# Sheet_f446.net
KiCad netlist of a schematic drawn in Altium Designer
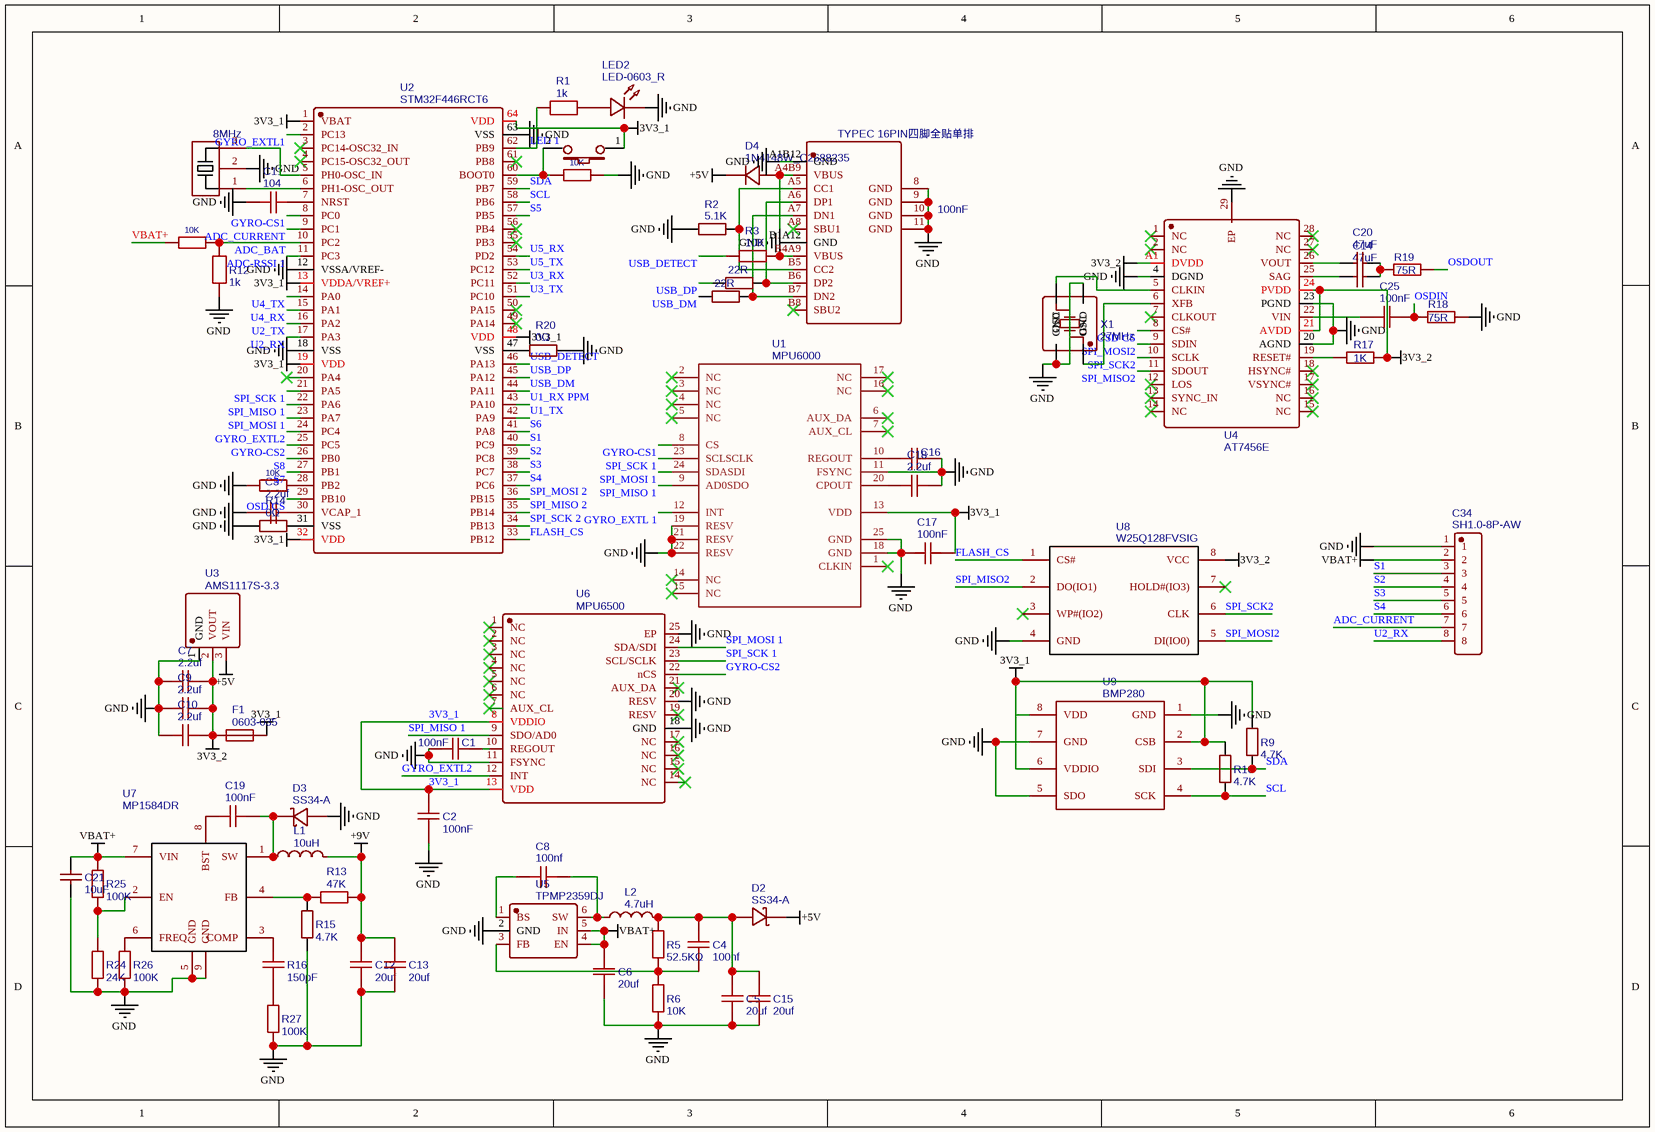
[diagram p0: Sheet_f446.schdoc]

(export (version "E")
  (design (tool "Eeschema 10.0.6"))
  (components
    (comp (ref "BOOT1")
      (value "两脚小龟 3*4*2")
      (fields (field (name "BOM_SUPPLIER PART") "C2837315") (field (name "CONTRIBUTOR") "LCSC"))
      (libsource (lib "altium-import") (part "root_2_两脚小龟 3*4*2_"))
    )
    (comp (ref "C1")
      (value "100nF")
      (fields
        (field (name "BOM_MANUFACTURER PART") "GRM155F50J104ZA01D")
        (field (name "BOM_SUPPLIER PART") "C85956")
      )
      (libsource (lib "altium-import") (part "root_0_100nF_"))
    )
    (comp (ref "C2")
      (value "100nF")
      (fields
        (field (name "BOM_MANUFACTURER PART") "GRM155F50J104ZA01D")
        (field (name "BOM_SUPPLIER PART") "C85956")
      )
      (libsource (lib "altium-import") (part "root_1_100nF_"))
    )
    (comp (ref "C3")
      (value "2.2uf")
      (fields (field (name "CONTRIBUTOR") "LCEDA_Lib"))
      (libsource (lib "altium-import") (part "root_2_2.2uf_"))
    )
    (comp (ref "C4")
      (value "100nf")
      (fields (field (name "BOM_MANUFACTURER PART") "CC0603FRNPO9BN201") (field (name "CONTRIBUTOR") "LCSC"))
      (libsource (lib "altium-import") (part "root_3_100nf_"))
    )
    (comp (ref "C5")
      (value "20uf")
      (fields (field (name "BOM_MANUFACTURER PART") "CC0603FRNPO9BN201") (field (name "CONTRIBUTOR") "LCSC"))
      (libsource (lib "altium-import") (part "root_3_20uf_"))
    )
    (comp (ref "C6")
      (value "20uf")
      (fields (field (name "BOM_MANUFACTURER PART") "CC0603FRNPO9BN201") (field (name "CONTRIBUTOR") "LCSC"))
      (libsource (lib "altium-import") (part "root_1_20uf_"))
    )
    (comp (ref "C7")
      (value "2.2uf")
      (fields (field (name "CONTRIBUTOR") "LCEDA_Lib"))
      (libsource (lib "altium-import") (part "root_0_2.2uf_"))
    )
    (comp (ref "C8")
      (value "100nf")
      (fields (field (name "BOM_MANUFACTURER PART") "CC0603FRNPO9BN201") (field (name "CONTRIBUTOR") "LCSC"))
      (libsource (lib "altium-import") (part "root_2_100nf_"))
    )
    (comp (ref "C9")
      (value "2.2uf")
      (fields (field (name "CONTRIBUTOR") "LCEDA_Lib"))
      (libsource (lib "altium-import") (part "root_2_2.2uf_"))
    )
    (comp (ref "C10")
      (value "2.2uf")
      (fields (field (name "CONTRIBUTOR") "LCEDA_Lib"))
      (libsource (lib "altium-import") (part "root_2_2.2uf_"))
    )
    (comp (ref "C11")
      (value "104")
      (fields (field (name "CONTRIBUTOR") "LCEDA_Lib"))
      (libsource (lib "altium-import") (part "root_2_104_"))
    )
    (comp (ref "C12")
      (value "20uf")
      (fields (field (name "BOM_MANUFACTURER PART") "CC0603FRNPO9BN201") (field (name "CONTRIBUTOR") "LCSC"))
      (libsource (lib "altium-import") (part "root_1_20uf_"))
    )
    (comp (ref "C13")
      (value "20uf")
      (fields (field (name "BOM_MANUFACTURER PART") "CC0603FRNPO9BN201") (field (name "CONTRIBUTOR") "LCSC"))
      (libsource (lib "altium-import") (part "root_1_20uf_"))
    )
    (comp (ref "C14")
      (value "47uF")
      (fields
        (field (name "BOM_MANUFACTURER PART") "CL21A476MQYNNNE")
        (field (name "BOM_SUPPLIER PART") "C16780")
      )
      (libsource (lib "altium-import") (part "root_0_47uF_"))
    )
    (comp (ref "C15")
      (value "20uf")
      (fields (field (name "BOM_MANUFACTURER PART") "CC0603FRNPO9BN201") (field (name "CONTRIBUTOR") "LCSC"))
      (libsource (lib "altium-import") (part "root_1_20uf_"))
    )
    (comp (ref "C16")
      (value "100nF")
      (fields
        (field (name "BOM_MANUFACTURER PART") "GRM155F50J104ZA01D")
        (field (name "BOM_SUPPLIER PART") "C85956")
      )
      (libsource (lib "altium-import") (part "root_0_100nF_"))
    )
    (comp (ref "C17")
      (value "100nF")
      (fields
        (field (name "BOM_MANUFACTURER PART") "GRM155F50J104ZA01D")
        (field (name "BOM_SUPPLIER PART") "C85956")
      )
      (libsource (lib "altium-import") (part "root_0_100nF_"))
    )
    (comp (ref "C18")
      (value "2.2uf")
      (fields (field (name "CONTRIBUTOR") "LCEDA_Lib"))
      (libsource (lib "altium-import") (part "root_0_2.2uf_"))
    )
    (comp (ref "C19")
      (value "100nF")
      (fields
        (field (name "BOM_MANUFACTURER PART") "CC0603KRX7R9BB104")
        (field (name "BOM_SUPPLIER PART") "C14663")
      )
      (libsource (lib "altium-import") (part "root_0_100nF_"))
    )
    (comp (ref "C20")
      (value "47uF")
      (fields
        (field (name "BOM_MANUFACTURER PART") "CL21A476MQYNNNE")
        (field (name "BOM_SUPPLIER PART") "C16780")
      )
      (libsource (lib "altium-import") (part "root_0_47uF_"))
    )
    (comp (ref "C21")
      (value "10uF")
      (fields
        (field (name "BOM_MANUFACTURER PART") "1206F106M500NT")
        (field (name "BOM_SUPPLIER PART") "C110256")
      )
      (libsource (lib "altium-import") (part "root_1_10uF_"))
    )
    (comp (ref "C25")
      (value "100nF")
      (fields
        (field (name "BOM_MANUFACTURER PART") "0402B104K500")
        (field (name "BOM_SUPPLIER PART") "C152814")
        (field (name "CONTRIBUTOR") "LCSC")
      )
      (libsource (lib "") (part "root_0_100nF__1"))
    )
    (comp (ref "C34")
      (value "SH1.0-8P-AW")
      (fields (field (name "CONTRIBUTOR") "xiogua"))
      (libsource (lib "altium-import") (part "root_0_SH1.0-8P-AW_"))
    )
    (comp (ref "D2")
      (value "SS34-A")
      (fields (field (name "BOM_SUPPLIER PART") "C143201") (field (name "CONTRIBUTOR") "LCSC"))
      (libsource (lib "altium-import") (part "root_2_SS34-A_"))
    )
    (comp (ref "D3")
      (value "SS34-A")
      (fields (field (name "BOM_SUPPLIER PART") "C143201") (field (name "CONTRIBUTOR") "LCSC"))
      (libsource (lib "altium-import") (part "root_0_SS34-A_"))
    )
    (comp (ref "D4")
      (value "1N4148W_C2688235")
      (fields
        (field (name "BOM_SUPPLIER PART") "C2688235")
        (field (name "BOM_MANUFACTURER PART") "1N4148W")
        (field (name "CONTRIBUTOR") "LCSC")
      )
      (libsource (lib "altium-import") (part "root_0_1N4148W_C2688235_"))
    )
    (comp (ref "F1")
      (value "0603-035")
      (fields (field (name "BOM_SUPPLIER PART") "C70051"))
      (libsource (lib "altium-import") (part "root_0_0603-035_"))
    )
    (comp (ref "L1")
      (value "10uH")
      (fields
        (field (name "BOM_MANUFACTURER PART") "MCW-0530-100-N1")
        (field (name "BOM_SUPPLIER PART") "C169352")
        (field (name "CONTRIBUTOR") "LCSC")
      )
      (libsource (lib "altium-import") (part "root_0_10uH_"))
    )
    (comp (ref "L2")
      (value "4.7uH")
      (fields
        (field (name "BOM_SUPPLIER PART") "C477143")
        (field (name "BOM_MANUFACTURER PART") "GPSR0420-4R7MS01")
        (field (name "CONTRIBUTOR") "LCSC")
      )
      (libsource (lib "altium-import") (part "root_0_4.7uH_"))
    )
    (comp (ref "LED2")
      (value "LED-0603_R")
      (fields
        (field (name "BOM_MANUFACTURER PART") "19-217/R6C-AL1M2VY/3T")
        (field (name "BOM_SUPPLIER PART") "C72044")
        (field (name "CONTRIBUTOR") "LCEDA_01")
      )
      (libsource (lib "altium-import") (part "root_0_LED-0603_R_"))
    )
    (comp (ref "NO")
      (value "TYPEC 16PIN四脚全贴单排")
      (fields (field (name "BOM_SUPPLIER PART") "C9900003589") (field (name "CONTRIBUTOR") "LCSC"))
      (libsource (lib "altium-import") (part "root_0_TYPEC 16PIN四脚全贴单排_"))
    )
    (comp (ref "R1")
      (value "1k")
      (fields (field (name "CONTRIBUTOR") "LCEDA_Lib"))
      (libsource (lib "altium-import") (part "root_0_1k_"))
    )
    (comp (ref "R2")
      (value "5.1K")
      (fields
        (field (name "BOM_MANUFACTURER PART") "RC0402DR-075K1L")
        (field (name "BOM_SUPPLIER PART") "C138073")
      )
      (libsource (lib "altium-import") (part "root_0_5.1K_"))
    )
    (comp (ref "R3")
      (value "10K")
      (fields
        (field (name "BOM_SUPPLIER PART") "C144807")
        (field (name "BOM_MANUFACTURER PART") "AC0402FR-0710KL")
        (field (name "CONTRIBUTOR") "LCSC")
      )
      (libsource (lib "altium-import") (part "root_0_10K_"))
    )
    (comp (ref "R4")
      (value "10K")
      (fields
        (field (name "BOM_SUPPLIER PART") "C84351")
        (field (name "BOM_MANUFACTURER PART") "TC0225B1002TCE")
        (field (name "CONTRIBUTOR") "LCSC")
      )
      (libsource (lib "altium-import") (part "root_2_10K_"))
    )
    (comp (ref "R5")
      (value "52.5KΩ")
      (fields
        (field (name "BOM_SUPPLIER PART") "C114978")
        (field (name "BOM_MANUFACTURER PART") "0402WGF523JTCE")
        (field (name "CONTRIBUTOR") "LCSC")
      )
      (libsource (lib "altium-import") (part "root_1_52.5KΩ_"))
    )
    (comp (ref "R6")
      (value "10K")
      (fields
        (field (name "BOM_MANUFACTURER PART") "AC0402JR-0710KL")
        (field (name "BOM_SUPPLIER PART") "C144731")
        (field (name "CONTRIBUTOR") "LCSC")
      )
      (libsource (lib "altium-import") (part "root_1_10K_"))
    )
    (comp (ref "R8")
      (value "10K")
      (fields
        (field (name "BOM_SUPPLIER PART") "C84351")
        (field (name "BOM_MANUFACTURER PART") "TC0225B1002TCE")
        (field (name "CONTRIBUTOR") "LCSC")
      )
      (libsource (lib "altium-import") (part "root_0_10K_"))
    )
    (comp (ref "R9")
      (value "4.7K")
      (fields
        (field (name "BOM_MANUFACTURER PART") "RC0402FR-074K7L")
        (field (name "BOM_SUPPLIER PART") "C105871")
      )
      (libsource (lib "altium-import") (part "root_1_4.7K_"))
    )
    (comp (ref "R10")
      (value "4.7K")
      (fields
        (field (name "BOM_MANUFACTURER PART") "RC0402FR-074K7L")
        (field (name "BOM_SUPPLIER PART") "C105871")
      )
      (libsource (lib "altium-import") (part "root_1_4.7K_"))
    )
    (comp (ref "R11")
      (value "10K")
      (fields
        (field (name "BOM_SUPPLIER PART") "C84351")
        (field (name "BOM_MANUFACTURER PART") "TC0225B1002TCE")
        (field (name "CONTRIBUTOR") "LCSC")
      )
      (libsource (lib "altium-import") (part "root_2_10K_"))
    )
    (comp (ref "R12")
      (value "1k")
      (fields (field (name "CONTRIBUTOR") "LCEDA_Lib"))
      (libsource (lib "altium-import") (part "root_1_1k_"))
    )
    (comp (ref "R13")
      (value "47K")
      (fields
        (field (name "BOM_MANUFACTURER PART") "AC0402JR-0747KL")
        (field (name "BOM_SUPPLIER PART") "C144710")
        (field (name "CONTRIBUTOR") "LCSC")
      )
      (libsource (lib "altium-import") (part "root_0_47K_"))
    )
    (comp (ref "R14")
      (value "0Ω")
      (fields (field (name "CONTRIBUTOR") "微客"))
      (libsource (lib "altium-import") (part "root_0_0Ω_"))
    )
    (comp (ref "R15")
      (value "4.7K")
      (fields
        (field (name "BOM_MANUFACTURER PART") "RC0402FR-074K7L")
        (field (name "BOM_SUPPLIER PART") "C105871")
      )
      (libsource (lib "altium-import") (part "root_1_4.7K_"))
    )
    (comp (ref "R16")
      (value "150pF")
      (fields
        (field (name "BOM_SUPPLIER PART") "C1623917")
        (field (name "BOM_MANUFACTURER PART") "C0402C151J8JAC7867")
        (field (name "CONTRIBUTOR") "LCSC")
      )
      (libsource (lib "altium-import") (part "root_1_150pF_"))
    )
    (comp (ref "R17")
      (value "1K")
      (fields
        (field (name "BOM_SUPPLIER PART") "C279987")
        (field (name "BOM_MANUFACTURER PART") "CR-02JL6----1K")
        (field (name "CONTRIBUTOR") "LCSC")
      )
      (libsource (lib "altium-import") (part "root_0_1K_"))
    )
    (comp (ref "R18")
      (value "75R")
      (fields
        (field (name "BOM_SUPPLIER PART") "C174263")
        (field (name "BOM_MANUFACTURER PART") "RCT0275RJLF")
        (field (name "CONTRIBUTOR") "LCSC")
      )
      (libsource (lib "altium-import") (part "root_0_75R_"))
    )
    (comp (ref "R19")
      (value "75R")
      (fields
        (field (name "BOM_SUPPLIER PART") "C174263")
        (field (name "BOM_MANUFACTURER PART") "RCT0275RJLF")
        (field (name "CONTRIBUTOR") "LCSC")
      )
      (libsource (lib "altium-import") (part "root_0_75R_"))
    )
    (comp (ref "R20")
      (value "0Ω")
      (fields (field (name "CONTRIBUTOR") "微客"))
      (libsource (lib "altium-import") (part "root_0_0Ω_"))
    )
    (comp (ref "R21")
      (value "22R")
      (fields
        (field (name "BOM_MANUFACTURER PART") "RM04FTN22R0")
        (field (name "BOM_SUPPLIER PART") "C153098")
      )
      (libsource (lib "altium-import") (part "root_2_22R_"))
    )
    (comp (ref "R22")
      (value "22R")
      (fields
        (field (name "BOM_MANUFACTURER PART") "RM04FTN22R0")
        (field (name "BOM_SUPPLIER PART") "C153098")
      )
      (libsource (lib "altium-import") (part "root_2_22R_"))
    )
    (comp (ref "R24")
      (value "24K")
      (fields
        (field (name "BOM_SUPPLIER PART") "C227339")
        (field (name "BOM_MANUFACTURER PART") "AC0402JR-0724KL")
        (field (name "CONTRIBUTOR") "LCSC")
      )
      (libsource (lib "altium-import") (part "root_1_24K_"))
    )
    (comp (ref "R25")
      (value "100K")
      (fields
        (field (name "BOM_MANUFACTURER PART") "AC0402JR-07100KL")
        (field (name "BOM_SUPPLIER PART") "C144732")
        (field (name "CONTRIBUTOR") "LCSC")
      )
      (libsource (lib "altium-import") (part "root_1_100K_"))
    )
    (comp (ref "R26")
      (value "100K")
      (fields
        (field (name "BOM_MANUFACTURER PART") "AC0402JR-07100KL")
        (field (name "BOM_SUPPLIER PART") "C144732")
        (field (name "CONTRIBUTOR") "LCSC")
      )
      (libsource (lib "altium-import") (part "root_1_100K_"))
    )
    (comp (ref "R27")
      (value "100K")
      (fields
        (field (name "BOM_MANUFACTURER PART") "AC0402JR-07100KL")
        (field (name "BOM_SUPPLIER PART") "C144732")
        (field (name "CONTRIBUTOR") "LCSC")
      )
      (libsource (lib "altium-import") (part "root_1_100K_"))
    )
    (comp (ref "U1")
      (value "MPU6000")
      (fields (field (name "CONTRIBUTOR") "msnrooon"))
      (libsource (lib "altium-import") (part "root_0_MPU6000_"))
    )
    (comp (ref "U2")
      (value "STM32F446RCT6")
      (fields (field (name "BOM_SUPPLIER PART") "C915971") (field (name "CONTRIBUTOR") "LCSC"))
      (libsource (lib "altium-import") (part "root_0_STM32F446RCT6_"))
    )
    (comp (ref "U3")
      (value "AMS1117S-3.3")
      (fields (field (name "BOM_SUPPLIER PART") "C917152") (field (name "CONTRIBUTOR") "LCSC"))
      (libsource (lib "altium-import") (part "root_1_AMS1117S-3.3_"))
    )
    (comp (ref "U4")
      (value "AT7456E")
      (fields (field (name "BOM_SUPPLIER PART") "C82351"))
      (libsource (lib "altium-import") (part "root_0_AT7456E_"))
    )
    (comp (ref "U5")
      (value "TPMP2359DJ")
      (fields (field (name "BOM_SUPPLIER PART") "C2959845") (field (name "CONTRIBUTOR") "LCSC"))
      (libsource (lib "altium-import") (part "root_0_TPMP2359DJ_"))
    )
    (comp (ref "U6")
      (value "MPU6500")
      (fields (field (name "BOM_SUPPLIER PART") "C50278"))
      (libsource (lib "altium-import") (part "root_0_MPU6500_"))
    )
    (comp (ref "U7")
      (value "MP1584DR")
      (fields (field (name "CONTRIBUTOR") "chejia12"))
      (libsource (lib "altium-import") (part "root_0_MP1584DR_"))
    )
    (comp (ref "U8")
      (value "W25Q128FVSIG")
      (fields (field (name "BOM_SUPPLIER PART") "C35101"))
      (libsource (lib "altium-import") (part "root_0_W25Q128FVSIG_"))
    )
    (comp (ref "U9")
      (value "BMP280")
      (fields (field (name "BOM_SUPPLIER PART") "C83291"))
      (libsource (lib "altium-import") (part "root_0_BMP280_"))
    )
    (comp (ref "X1")
      (value "27MHz")
      (fields
        (field (name "BOM_SUPPLIER PART") "C438902")
        (field (name "BOM_MANUFACTURER PART") "NX2016SA-STD-CZS-5-27MHZ")
        (field (name "CONTRIBUTOR") "LCSC")
      )
      (libsource (lib "altium-import") (part "root_1_27MHz_"))
    )
    (comp (ref "X3")
      (value "8MHz")
      (fields
        (field (name "BOM_MANUFACTURER PART") "CSTCE8M00G55A-R0")
        (field (name "BOM_SUPPLIER PART") "C91587")
      )
      (libsource (lib "altium-import") (part "root_1_8MHz_"))
    )
  )
  (nets
    (net (code "1") (name "+5V") (class "Default")
      (node (ref "D2") (pin "1") (pinfunction "C_1") (pintype "passive"))
      (node (ref "D4") (pin "1") (pinfunction "K_1") (pintype "passive"))
      (node (ref "U3") (pin "3") (pinfunction "VIN_3") (pintype "passive"))
    )
    (net (code "2") (name "+9V") (class "Default")
      (node (ref "C12") (pin "2") (pinfunction "2_2") (pintype "passive"))
      (node (ref "C13") (pin "2") (pinfunction "2_2") (pintype "passive"))
      (node (ref "L1") (pin "2") (pinfunction "2_2") (pintype "passive"))
      (node (ref "R13") (pin "2") (pinfunction "2_2") (pintype "passive"))
    )
    (net (code "3") (name "/ADC-RSSI 1") (class "Default")
      (node (ref "U2") (pin "11") (pinfunction "PC3_11") (pintype "passive"))
    )
    (net (code "4") (name "/ADC_BAT") (class "Default")
      (node (ref "R11") (pin "1") (pinfunction "1_1") (pintype "passive"))
      (node (ref "R12") (pin "2") (pinfunction "2_2") (pintype "passive"))
      (node (ref "U2") (pin "10") (pinfunction "PC2_10") (pintype "passive"))
    )
    (net (code "5") (name "/ADC_CURRENT") (class "Default")
      (node (ref "C34") (pin "7") (pinfunction "7_7") (pintype "passive"))
      (node (ref "U2") (pin "9") (pinfunction "PC1_9") (pintype "passive"))
    )
    (net (code "6") (name "/FLASH_CS") (class "Default")
      (node (ref "U2") (pin "33") (pinfunction "PB12_33") (pintype "passive"))
      (node (ref "U8") (pin "1") (pinfunction "CS#_1") (pintype "passive"))
    )
    (net (code "7") (name "/GYRO-CS1") (class "Default")
      (node (ref "U1") (pin "8") (pinfunction "CS_8") (pintype "passive"))
      (node (ref "U2") (pin "8") (pinfunction "PC0_8") (pintype "passive"))
    )
    (net (code "8") (name "/GYRO-CS2") (class "Default")
      (node (ref "U2") (pin "25") (pinfunction "PC5_25") (pintype "passive"))
      (node (ref "U6") (pin "22") (pinfunction "nCS_22") (pintype "passive"))
    )
    (net (code "9") (name "/GYRO_EXTL 1") (class "Default")
      (node (ref "U1") (pin "12") (pinfunction "INT_12") (pintype "passive"))
    )
    (net (code "10") (name "/GYRO_EXTL1") (class "Default")
      (node (ref "U2") (pin "2") (pinfunction "PC13_2") (pintype "passive"))
    )
    (net (code "11") (name "/GYRO_EXTL2") (class "Default")
      (node (ref "U2") (pin "24") (pinfunction "PC4_24") (pintype "passive"))
      (node (ref "U6") (pin "12") (pinfunction "INT_12") (pintype "passive"))
    )
    (net (code "12") (name "/LED 1") (class "Default")
      (node (ref "R1") (pin "1") (pinfunction "1_1") (pintype "passive"))
      (node (ref "U2") (pin "62") (pinfunction "PB9_62") (pintype "passive"))
    )
    (net (code "13") (name "/OSD CS") (class "Default")
      (node (ref "U2") (pin "29") (pinfunction "PB10_29") (pintype "passive"))
      (node (ref "U4") (pin "8") (pinfunction "CS#_8") (pintype "passive"))
    )
    (net (code "14") (name "/OSDIN") (class "Default")
      (node (ref "C25") (pin "1") (pinfunction "1_1") (pintype "passive"))
      (node (ref "R18") (pin "1") (pinfunction "1_1") (pintype "passive"))
    )
    (net (code "15") (name "/OSDOUT") (class "Default")
      (node (ref "R19") (pin "2") (pinfunction "2_2") (pintype "passive"))
    )
    (net (code "16") (name "/S1") (class "Default")
      (node (ref "C34") (pin "3") (pinfunction "3_3") (pintype "passive"))
      (node (ref "U2") (pin "40") (pinfunction "PC9_40") (pintype "passive"))
    )
    (net (code "17") (name "/S2") (class "Default")
      (node (ref "C34") (pin "4") (pinfunction "4_4") (pintype "passive"))
      (node (ref "U2") (pin "39") (pinfunction "PC8_39") (pintype "passive"))
    )
    (net (code "18") (name "/S3") (class "Default")
      (node (ref "C34") (pin "5") (pinfunction "5_5") (pintype "passive"))
      (node (ref "U2") (pin "38") (pinfunction "PC7_38") (pintype "passive"))
    )
    (net (code "19") (name "/S4") (class "Default")
      (node (ref "C34") (pin "6") (pinfunction "6_6") (pintype "passive"))
      (node (ref "U2") (pin "37") (pinfunction "PC6_37") (pintype "passive"))
    )
    (net (code "20") (name "/S5") (class "Default")
      (node (ref "U2") (pin "57") (pinfunction "PB5_57") (pintype "passive"))
    )
    (net (code "21") (name "/S6") (class "Default")
      (node (ref "U2") (pin "41") (pinfunction "PA8_41") (pintype "passive"))
    )
    (net (code "22") (name "/S7") (class "Default")
      (node (ref "U2") (pin "27") (pinfunction "PB1_27") (pintype "passive"))
    )
    (net (code "23") (name "/S8") (class "Default")
      (node (ref "U2") (pin "26") (pinfunction "PB0_26") (pintype "passive"))
    )
    (net (code "24") (name "/SCL") (class "Default")
      (node (ref "R10") (pin "1") (pinfunction "1_1") (pintype "passive"))
      (node (ref "U2") (pin "58") (pinfunction "PB6_58") (pintype "passive"))
      (node (ref "U9") (pin "4") (pinfunction "SCK_4") (pintype "passive"))
    )
    (net (code "25") (name "/SDA") (class "Default")
      (node (ref "R9") (pin "1") (pinfunction "1_1") (pintype "passive"))
      (node (ref "U2") (pin "59") (pinfunction "PB7_59") (pintype "passive"))
      (node (ref "U9") (pin "3") (pinfunction "SDI_3") (pintype "passive"))
    )
    (net (code "26") (name "/SPI_MISO 1") (class "Default")
      (node (ref "U1") (pin "9") (pinfunction "AD0SDO_9") (pintype "passive"))
      (node (ref "U2") (pin "22") (pinfunction "PA6_22") (pintype "passive"))
      (node (ref "U6") (pin "9") (pinfunction "SDO/AD0_9") (pintype "passive"))
    )
    (net (code "27") (name "/SPI_MISO 2") (class "Default")
      (node (ref "U2") (pin "35") (pinfunction "PB14_35") (pintype "passive"))
    )
    (net (code "28") (name "/SPI_MISO2") (class "Default")
      (node (ref "U4") (pin "11") (pinfunction "SDOUT_11") (pintype "passive"))
      (node (ref "U8") (pin "2") (pinfunction "DO(IO1)_2") (pintype "passive"))
    )
    (net (code "29") (name "/SPI_MOSI 1") (class "Default")
      (node (ref "U1") (pin "24") (pinfunction "SDASDI_24") (pintype "passive"))
      (node (ref "U2") (pin "23") (pinfunction "PA7_23") (pintype "passive"))
      (node (ref "U6") (pin "24") (pinfunction "SDA/SDI_24") (pintype "passive"))
    )
    (net (code "30") (name "/SPI_MOSI 2") (class "Default")
      (node (ref "U2") (pin "36") (pinfunction "PB15_36") (pintype "passive"))
    )
    (net (code "31") (name "/SPI_MOSI2") (class "Default")
      (node (ref "U4") (pin "9") (pinfunction "SDIN_9") (pintype "passive"))
      (node (ref "U8") (pin "5") (pinfunction "DI(IO0)_5") (pintype "passive"))
    )
    (net (code "32") (name "/SPI_SCK 1") (class "Default")
      (node (ref "U1") (pin "23") (pinfunction "SCLSCLK_23") (pintype "passive"))
      (node (ref "U2") (pin "21") (pinfunction "PA5_21") (pintype "passive"))
      (node (ref "U6") (pin "23") (pinfunction "SCL/SCLK_23") (pintype "passive"))
    )
    (net (code "33") (name "/SPI_SCK 2") (class "Default")
      (node (ref "U2") (pin "34") (pinfunction "PB13_34") (pintype "passive"))
    )
    (net (code "34") (name "/SPI_SCK2") (class "Default")
      (node (ref "U4") (pin "10") (pinfunction "SCLK_10") (pintype "passive"))
      (node (ref "U8") (pin "6") (pinfunction "CLK_6") (pintype "passive"))
    )
    (net (code "35") (name "/U1_RX PPM") (class "Default")
      (node (ref "U2") (pin "43") (pinfunction "PA10_43") (pintype "passive"))
    )
    (net (code "36") (name "/U1_TX") (class "Default")
      (node (ref "U2") (pin "42") (pinfunction "PA9_42") (pintype "passive"))
    )
    (net (code "37") (name "/U2_RX") (class "Default")
      (node (ref "C34") (pin "8") (pinfunction "8_8") (pintype "passive"))
      (node (ref "U2") (pin "17") (pinfunction "PA3_17") (pintype "passive"))
    )
    (net (code "38") (name "/U2_TX") (class "Default")
      (node (ref "U2") (pin "16") (pinfunction "PA2_16") (pintype "passive"))
    )
    (net (code "39") (name "/U3_RX") (class "Default")
      (node (ref "U2") (pin "52") (pinfunction "PC11_52") (pintype "passive"))
    )
    (net (code "40") (name "/U3_TX") (class "Default")
      (node (ref "U2") (pin "51") (pinfunction "PC10_51") (pintype "passive"))
    )
    (net (code "41") (name "/U4_RX") (class "Default")
      (node (ref "U2") (pin "15") (pinfunction "PA1_15") (pintype "passive"))
    )
    (net (code "42") (name "/U4_TX") (class "Default")
      (node (ref "U2") (pin "14") (pinfunction "PA0_14") (pintype "passive"))
    )
    (net (code "43") (name "/U5_RX") (class "Default")
      (node (ref "U2") (pin "54") (pinfunction "PD2_54") (pintype "passive"))
    )
    (net (code "44") (name "/U5_TX") (class "Default")
      (node (ref "U2") (pin "53") (pinfunction "PC12_53") (pintype "passive"))
    )
    (net (code "45") (name "/USB_DETECT") (class "Default")
      (node (ref "R3") (pin "1") (pinfunction "1_1") (pintype "passive"))
      (node (ref "U2") (pin "46") (pinfunction "PA13_46") (pintype "passive"))
    )
    (net (code "46") (name "/USB_DM") (class "Default")
      (node (ref "R22") (pin "2") (pinfunction "2_2") (pintype "passive"))
      (node (ref "U2") (pin "44") (pinfunction "PA11_44") (pintype "passive"))
    )
    (net (code "47") (name "/USB_DP") (class "Default")
      (node (ref "R21") (pin "2") (pinfunction "2_2") (pintype "passive"))
      (node (ref "U2") (pin "45") (pinfunction "PA12_45") (pintype "passive"))
    )
    (net (code "48") (name "3V3_1") (class "Default")
      (node (ref "BOOT1") (pin "1") (pinfunction "1_1") (pintype "passive"))
      (node (ref "C17") (pin "2") (pinfunction "2_2") (pintype "passive"))
      (node (ref "C2") (pin "2") (pinfunction "2_2") (pintype "passive"))
      (node (ref "F1") (pin "2") (pinfunction "2_2") (pintype "passive"))
      (node (ref "R10") (pin "2") (pinfunction "2_2") (pintype "passive"))
      (node (ref "R9") (pin "2") (pinfunction "2_2") (pintype "passive"))
      (node (ref "U1") (pin "13") (pinfunction "VDD_13") (pintype "passive"))
      (node (ref "U2") (pin "1") (pinfunction "VBAT_1") (pintype "passive"))
      (node (ref "U2") (pin "13") (pinfunction "VDDA/VREF+_13") (pintype "passive"))
      (node (ref "U2") (pin "19") (pinfunction "VDD_19") (pintype "passive"))
      (node (ref "U2") (pin "32") (pinfunction "VDD_32") (pintype "passive"))
      (node (ref "U2") (pin "48") (pinfunction "VDD_48") (pintype "passive"))
      (node (ref "U2") (pin "64") (pinfunction "VDD_64") (pintype "passive"))
      (node (ref "U6") (pin "13") (pinfunction "VDD_13") (pintype "passive"))
      (node (ref "U6") (pin "8") (pinfunction "VDDIO_8") (pintype "passive"))
      (node (ref "U9") (pin "2") (pinfunction "CSB_2") (pintype "passive"))
      (node (ref "U9") (pin "6") (pinfunction "VDDIO_6") (pintype "passive"))
      (node (ref "U9") (pin "8") (pinfunction "VDD_8") (pintype "passive"))
    )
    (net (code "49") (name "3V3_2") (class "Default")
      (node (ref "C10") (pin "1") (pinfunction "1_1") (pintype "passive"))
      (node (ref "C7") (pin "2") (pinfunction "2_2") (pintype "passive"))
      (node (ref "C9") (pin "1") (pinfunction "1_1") (pintype "passive"))
      (node (ref "F1") (pin "1") (pinfunction "1_1") (pintype "passive"))
      (node (ref "R17") (pin "2") (pinfunction "2_2") (pintype "passive"))
      (node (ref "U3") (pin "2") (pinfunction "VOUT_2") (pintype "passive"))
      (node (ref "U4") (pin "21") (pinfunction "AVDD_21") (pintype "passive"))
      (node (ref "U4") (pin "24") (pinfunction "PVDD_24") (pintype "passive"))
      (node (ref "U4") (pin "A1") (pinfunction "DVDD_A1") (pintype "passive"))
      (node (ref "U8") (pin "8") (pinfunction "VCC_8") (pintype "passive"))
    )
    (net (code "50") (name "GND") (class "Default")
      (node (ref "C1") (pin "1") (pinfunction "1_1") (pintype "passive"))
      (node (ref "C10") (pin "2") (pinfunction "2_2") (pintype "passive"))
      (node (ref "C11") (pin "2") (pinfunction "2_2") (pintype "passive"))
      (node (ref "C12") (pin "1") (pinfunction "1_1") (pintype "passive"))
      (node (ref "C13") (pin "1") (pinfunction "1_1") (pintype "passive"))
      (node (ref "C15") (pin "1") (pinfunction "1_1") (pintype "passive"))
      (node (ref "C16") (pin "2") (pinfunction "2_2") (pintype "passive"))
      (node (ref "C17") (pin "1") (pinfunction "1_1") (pintype "passive"))
      (node (ref "C18") (pin "2") (pinfunction "2_2") (pintype "passive"))
      (node (ref "C2") (pin "1") (pinfunction "1_1") (pintype "passive"))
      (node (ref "C21") (pin "1") (pinfunction "1_1") (pintype "passive"))
      (node (ref "C3") (pin "2") (pinfunction "2_2") (pintype "passive"))
      (node (ref "C34") (pin "1") (pinfunction "1_1") (pintype "passive"))
      (node (ref "C5") (pin "2") (pinfunction "2_2") (pintype "passive"))
      (node (ref "C6") (pin "1") (pinfunction "1_1") (pintype "passive"))
      (node (ref "C7") (pin "1") (pinfunction "1_1") (pintype "passive"))
      (node (ref "C9") (pin "2") (pinfunction "2_2") (pintype "passive"))
      (node (ref "D3") (pin "2") (pinfunction "A_2") (pintype "passive"))
      (node (ref "LED2") (pin "2") (pinfunction "2_2") (pintype "passive"))
      (node (ref "NO") (pin "10") (pinfunction "GND_10") (pintype "passive"))
      (node (ref "NO") (pin "11") (pinfunction "GND_11") (pintype "passive"))
      (node (ref "NO") (pin "8") (pinfunction "GND_8") (pintype "passive"))
      (node (ref "NO") (pin "9") (pinfunction "GND_9") (pintype "passive"))
      (node (ref "NO") (pin "A1B12") (pinfunction "GND_A1B12") (pintype "passive"))
      (node (ref "NO") (pin "B1A12") (pinfunction "GND_B1A12") (pintype "passive"))
      (node (ref "R12") (pin "1") (pinfunction "1_1") (pintype "passive"))
      (node (ref "R14") (pin "1") (pinfunction "1_1") (pintype "passive"))
      (node (ref "R15") (pin "1") (pinfunction "1_1") (pintype "passive"))
      (node (ref "R18") (pin "2") (pinfunction "2_2") (pintype "passive"))
      (node (ref "R2") (pin "1") (pinfunction "1_1") (pintype "passive"))
      (node (ref "R20") (pin "2") (pinfunction "2_2") (pintype "passive"))
      (node (ref "R24") (pin "1") (pinfunction "1_1") (pintype "passive"))
      (node (ref "R26") (pin "1") (pinfunction "1_1") (pintype "passive"))
      (node (ref "R27") (pin "1") (pinfunction "1_1") (pintype "passive"))
      (node (ref "R4") (pin "1") (pinfunction "1_1") (pintype "passive"))
      (node (ref "R6") (pin "1") (pinfunction "1_1") (pintype "passive"))
      (node (ref "R8") (pin "1") (pinfunction "1_1") (pintype "passive"))
      (node (ref "U1") (pin "11") (pinfunction "FSYNC_11") (pintype "passive"))
      (node (ref "U1") (pin "18") (pinfunction "GND_18") (pintype "passive"))
      (node (ref "U1") (pin "19") (pinfunction "RESV_19") (pintype "passive"))
      (node (ref "U1") (pin "21") (pinfunction "RESV_21") (pintype "passive"))
      (node (ref "U1") (pin "22") (pinfunction "RESV_22") (pintype "passive"))
      (node (ref "U1") (pin "25") (pinfunction "GND_25") (pintype "passive"))
      (node (ref "U2") (pin "12") (pinfunction "VSSA/VREF-_12") (pintype "passive"))
      (node (ref "U2") (pin "18") (pinfunction "VSS_18") (pintype "passive"))
      (node (ref "U2") (pin "63") (pinfunction "VSS_63") (pintype "passive"))
      (node (ref "U3") (pin "1") (pinfunction "GND_1") (pintype "passive"))
      (node (ref "U4") (pin "20") (pinfunction "AGND_20") (pintype "passive"))
      (node (ref "U4") (pin "23") (pinfunction "PGND_23") (pintype "passive"))
      (node (ref "U4") (pin "29") (pinfunction "EP_29") (pintype "passive"))
      (node (ref "U4") (pin "4") (pinfunction "DGND_4") (pintype "passive"))
      (node (ref "U5") (pin "2") (pinfunction "GND_2") (pintype "passive"))
      (node (ref "U6") (pin "11") (pinfunction "FSYNC_11") (pintype "passive"))
      (node (ref "U6") (pin "18") (pinfunction "GND_18") (pintype "passive"))
      (node (ref "U6") (pin "20") (pinfunction "RESV_20") (pintype "passive"))
      (node (ref "U6") (pin "25") (pinfunction "EP_25") (pintype "passive"))
      (node (ref "U7") (pin "5") (pinfunction "GND_5") (pintype "passive"))
      (node (ref "U7") (pin "9") (pinfunction "GND_9") (pintype "passive"))
      (node (ref "U8") (pin "4") (pinfunction "GND_4") (pintype "passive"))
      (node (ref "U9") (pin "1") (pinfunction "GND_1") (pintype "passive"))
      (node (ref "U9") (pin "5") (pinfunction "SDO_5") (pintype "passive"))
      (node (ref "U9") (pin "7") (pinfunction "GND_7") (pintype "passive"))
      (node (ref "X1") (pin "2") (pinfunction "GND_2") (pintype "passive"))
      (node (ref "X1") (pin "4") (pinfunction "GND_4") (pintype "passive"))
      (node (ref "X3") (pin "2") (pinfunction "2_2") (pintype "passive"))
    )
    (net (code "51") (name "Net-(C14-Pad2)") (class "Default")
      (node (ref "C14") (pin "2") (pinfunction "2_2") (pintype "passive"))
      (node (ref "C20") (pin "2") (pinfunction "2_2") (pintype "passive"))
      (node (ref "R19") (pin "1") (pinfunction "1_1") (pintype "passive"))
    )
    (net (code "52") (name "Net-(D2-A)") (class "Default")
      (node (ref "C15") (pin "2") (pinfunction "2_2") (pintype "passive"))
      (node (ref "C4") (pin "1") (pinfunction "1_1") (pintype "passive"))
      (node (ref "C5") (pin "1") (pinfunction "1_1") (pintype "passive"))
      (node (ref "D2") (pin "2") (pinfunction "A_2") (pintype "passive"))
      (node (ref "L2") (pin "2") (pinfunction "2_2") (pintype "passive"))
      (node (ref "R5") (pin "2") (pinfunction "2_2") (pintype "passive"))
    )
    (net (code "53") (name "Net-(D3-C)") (class "Default")
      (node (ref "C19") (pin "2") (pinfunction "2_2") (pintype "passive"))
      (node (ref "D3") (pin "1") (pinfunction "C_1") (pintype "passive"))
      (node (ref "L1") (pin "1") (pinfunction "1_1") (pintype "passive"))
      (node (ref "U7") (pin "1") (pinfunction "SW_1") (pintype "passive"))
    )
    (net (code "54") (name "Net-(D4-A)") (class "Default")
      (node (ref "D4") (pin "2") (pinfunction "A_2") (pintype "passive"))
      (node (ref "NO") (pin "A4B9") (pinfunction "VBUS_A4B9") (pintype "passive"))
      (node (ref "NO") (pin "B4A9") (pinfunction "VBUS_B4A9") (pintype "passive"))
      (node (ref "R3") (pin "2") (pinfunction "2_2") (pintype "passive"))
    )
    (net (code "55") (name "Net-(LED2-Pad1)") (class "Default")
      (node (ref "LED2") (pin "1") (pinfunction "1_1") (pintype "passive"))
      (node (ref "R1") (pin "2") (pinfunction "2_2") (pintype "passive"))
    )
    (net (code "56") (name "Net-(NO-CC1)") (class "Default")
      (node (ref "NO") (pin "A5") (pinfunction "CC1_A5") (pintype "passive"))
      (node (ref "NO") (pin "B5") (pinfunction "CC2_B5") (pintype "passive"))
      (node (ref "R2") (pin "2") (pinfunction "2_2") (pintype "passive"))
    )
    (net (code "57") (name "Net-(NO-DN1)") (class "Default")
      (node (ref "NO") (pin "A7") (pinfunction "DN1_A7") (pintype "passive"))
      (node (ref "NO") (pin "B7") (pinfunction "DN2_B7") (pintype "passive"))
      (node (ref "R22") (pin "1") (pinfunction "1_1") (pintype "passive"))
    )
    (net (code "58") (name "Net-(NO-DP1)") (class "Default")
      (node (ref "NO") (pin "A6") (pinfunction "DP1_A6") (pintype "passive"))
      (node (ref "NO") (pin "B6") (pinfunction "DP2_B6") (pintype "passive"))
      (node (ref "R21") (pin "1") (pinfunction "1_1") (pintype "passive"))
    )
    (net (code "59") (name "Net-(R14-Pad2)") (class "Default")
      (node (ref "R14") (pin "2") (pinfunction "2_2") (pintype "passive"))
      (node (ref "U2") (pin "31") (pinfunction "VSS_31") (pintype "passive"))
    )
    (net (code "60") (name "Net-(R16-Pad1)") (class "Default")
      (node (ref "R16") (pin "1") (pinfunction "1_1") (pintype "passive"))
      (node (ref "R27") (pin "2") (pinfunction "2_2") (pintype "passive"))
    )
    (net (code "61") (name "Net-(R20-Pad1)") (class "Default")
      (node (ref "R20") (pin "1") (pinfunction "1_1") (pintype "passive"))
      (node (ref "U2") (pin "47") (pinfunction "VSS_47") (pintype "passive"))
    )
    (net (code "62") (name "Net-(U1-CPOUT)") (class "Default")
      (node (ref "C18") (pin "1") (pinfunction "1_1") (pintype "passive"))
      (node (ref "U1") (pin "20") (pinfunction "CPOUT_20") (pintype "passive"))
    )
    (net (code "63") (name "Net-(U1-REGOUT)") (class "Default")
      (node (ref "C16") (pin "1") (pinfunction "1_1") (pintype "passive"))
      (node (ref "U1") (pin "10") (pinfunction "REGOUT_10") (pintype "passive"))
    )
    (net (code "64") (name "Net-(U2-BOOT0)") (class "Default")
      (node (ref "BOOT1") (pin "2") (pinfunction "2_2") (pintype "passive"))
      (node (ref "R4") (pin "2") (pinfunction "2_2") (pintype "passive"))
      (node (ref "U2") (pin "60") (pinfunction "BOOT0_60") (pintype "passive"))
    )
    (net (code "65") (name "Net-(U2-NRST)") (class "Default")
      (node (ref "C11") (pin "1") (pinfunction "1_1") (pintype "passive"))
      (node (ref "U2") (pin "7") (pinfunction "NRST_7") (pintype "passive"))
    )
    (net (code "66") (name "Net-(U2-PB2)") (class "Default")
      (node (ref "R8") (pin "2") (pinfunction "2_2") (pintype "passive"))
      (node (ref "U2") (pin "28") (pinfunction "PB2_28") (pintype "passive"))
    )
    (net (code "67") (name "Net-(U2-PH0-OSC_IN)") (class "Default")
      (node (ref "U2") (pin "5") (pinfunction "PH0-OSC_IN_5") (pintype "passive"))
      (node (ref "X3") (pin "3") (pinfunction "3_3") (pintype "passive"))
    )
    (net (code "68") (name "Net-(U2-PH1-OSC_OUT)") (class "Default")
      (node (ref "U2") (pin "6") (pinfunction "PH1-OSC_OUT_6") (pintype "passive"))
      (node (ref "X3") (pin "1") (pinfunction "1_1") (pintype "passive"))
    )
    (net (code "69") (name "Net-(U2-VCAP_1)") (class "Default")
      (node (ref "C3") (pin "1") (pinfunction "1_1") (pintype "passive"))
      (node (ref "U2") (pin "30") (pinfunction "VCAP_1_30") (pintype "passive"))
    )
    (net (code "70") (name "Net-(U4-CLKIN)") (class "Default")
      (node (ref "U4") (pin "5") (pinfunction "CLKIN_5") (pintype "passive"))
      (node (ref "X1") (pin "3") (pinfunction "OSC_3") (pintype "passive"))
    )
    (net (code "71") (name "Net-(U4-RESET#)") (class "Default")
      (node (ref "R17") (pin "1") (pinfunction "1_1") (pintype "passive"))
      (node (ref "U4") (pin "19") (pinfunction "RESET#_19") (pintype "passive"))
    )
    (net (code "72") (name "Net-(U4-SAG)") (class "Default")
      (node (ref "C14") (pin "1") (pinfunction "1_1") (pintype "passive"))
      (node (ref "U4") (pin "25") (pinfunction "SAG_25") (pintype "passive"))
    )
    (net (code "73") (name "Net-(U4-VIN)") (class "Default")
      (node (ref "C25") (pin "2") (pinfunction "2_2") (pintype "passive"))
      (node (ref "U4") (pin "22") (pinfunction "VIN_22") (pintype "passive"))
    )
    (net (code "74") (name "Net-(U4-VOUT)") (class "Default")
      (node (ref "C20") (pin "1") (pinfunction "1_1") (pintype "passive"))
      (node (ref "U4") (pin "26") (pinfunction "VOUT_26") (pintype "passive"))
    )
    (net (code "75") (name "Net-(U4-XFB)") (class "Default")
      (node (ref "U4") (pin "6") (pinfunction "XFB_6") (pintype "passive"))
      (node (ref "X1") (pin "1") (pinfunction "OSC_1") (pintype "passive"))
    )
    (net (code "76") (name "Net-(U5-BS)") (class "Default")
      (node (ref "C8") (pin "2") (pinfunction "2_2") (pintype "passive"))
      (node (ref "U5") (pin "1") (pinfunction "BS_1") (pintype "passive"))
    )
    (net (code "77") (name "Net-(U5-FB)") (class "Default")
      (node (ref "C4") (pin "2") (pinfunction "2_2") (pintype "passive"))
      (node (ref "R5") (pin "1") (pinfunction "1_1") (pintype "passive"))
      (node (ref "R6") (pin "2") (pinfunction "2_2") (pintype "passive"))
      (node (ref "U5") (pin "3") (pinfunction "FB_3") (pintype "passive"))
    )
    (net (code "78") (name "Net-(U5-SW)") (class "Default")
      (node (ref "C8") (pin "1") (pinfunction "1_1") (pintype "passive"))
      (node (ref "L2") (pin "1") (pinfunction "1_1") (pintype "passive"))
      (node (ref "U5") (pin "6") (pinfunction "SW_6") (pintype "passive"))
    )
    (net (code "79") (name "Net-(U6-REGOUT)") (class "Default")
      (node (ref "C1") (pin "2") (pinfunction "2_2") (pintype "passive"))
      (node (ref "U6") (pin "10") (pinfunction "REGOUT_10") (pintype "passive"))
    )
    (net (code "80") (name "Net-(U7-BST)") (class "Default")
      (node (ref "C19") (pin "1") (pinfunction "1_1") (pintype "passive"))
      (node (ref "U7") (pin "8") (pinfunction "BST_8") (pintype "passive"))
    )
    (net (code "81") (name "Net-(U7-COMP)") (class "Default")
      (node (ref "R16") (pin "2") (pinfunction "2_2") (pintype "passive"))
      (node (ref "U7") (pin "3") (pinfunction "COMP_3") (pintype "passive"))
    )
    (net (code "82") (name "Net-(U7-EN)") (class "Default")
      (node (ref "R24") (pin "2") (pinfunction "2_2") (pintype "passive"))
      (node (ref "R25") (pin "1") (pinfunction "1_1") (pintype "passive"))
      (node (ref "U7") (pin "2") (pinfunction "EN_2") (pintype "passive"))
    )
    (net (code "83") (name "Net-(U7-FB)") (class "Default")
      (node (ref "R13") (pin "1") (pinfunction "1_1") (pintype "passive"))
      (node (ref "R15") (pin "2") (pinfunction "2_2") (pintype "passive"))
      (node (ref "U7") (pin "4") (pinfunction "FB_4") (pintype "passive"))
    )
    (net (code "84") (name "Net-(U7-FREQ.)") (class "Default")
      (node (ref "R26") (pin "2") (pinfunction "2_2") (pintype "passive"))
      (node (ref "U7") (pin "6") (pinfunction "FREQ._6") (pintype "passive"))
    )
    (net (code "85") (name "VBAT+") (class "Default")
      (node (ref "C21") (pin "2") (pinfunction "2_2") (pintype "passive"))
      (node (ref "C34") (pin "2") (pinfunction "2_2") (pintype "passive"))
      (node (ref "C6") (pin "2") (pinfunction "2_2") (pintype "passive"))
      (node (ref "R11") (pin "2") (pinfunction "2_2") (pintype "passive"))
      (node (ref "R25") (pin "2") (pinfunction "2_2") (pintype "passive"))
      (node (ref "U5") (pin "4") (pinfunction "EN_4") (pintype "passive"))
      (node (ref "U5") (pin "5") (pinfunction "IN_5") (pintype "passive"))
      (node (ref "U7") (pin "7") (pinfunction "VIN_7") (pintype "passive"))
    )
    (net (code "86") (name "unconnected-(NO-SBU1-PadA8)") (class "Default")
      (node (ref "NO") (pin "A8") (pinfunction "SBU1_A8") (pintype "passive+no_connect"))
    )
    (net (code "87") (name "unconnected-(NO-SBU2-PadB8)") (class "Default")
      (node (ref "NO") (pin "B8") (pinfunction "SBU2_B8") (pintype "passive+no_connect"))
    )
    (net (code "88") (name "unconnected-(U1-AUX_CL-Pad7)") (class "Default")
      (node (ref "U1") (pin "7") (pinfunction "AUX_CL_7") (pintype "passive+no_connect"))
    )
    (net (code "89") (name "unconnected-(U1-AUX_DA-Pad6)") (class "Default")
      (node (ref "U1") (pin "6") (pinfunction "AUX_DA_6") (pintype "passive+no_connect"))
    )
    (net (code "90") (name "unconnected-(U1-CLKIN-Pad1)") (class "Default")
      (node (ref "U1") (pin "1") (pinfunction "CLKIN_1") (pintype "passive+no_connect"))
    )
    (net (code "91") (name "unconnected-(U1-NC-Pad2)") (class "Default")
      (node (ref "U1") (pin "2") (pinfunction "NC_2") (pintype "passive+no_connect"))
    )
    (net (code "92") (name "unconnected-(U1-NC-Pad3)") (class "Default")
      (node (ref "U1") (pin "3") (pinfunction "NC_3") (pintype "passive+no_connect"))
    )
    (net (code "93") (name "unconnected-(U1-NC-Pad4)") (class "Default")
      (node (ref "U1") (pin "4") (pinfunction "NC_4") (pintype "passive+no_connect"))
    )
    (net (code "94") (name "unconnected-(U1-NC-Pad5)") (class "Default")
      (node (ref "U1") (pin "5") (pinfunction "NC_5") (pintype "passive+no_connect"))
    )
    (net (code "95") (name "unconnected-(U1-NC-Pad14)") (class "Default")
      (node (ref "U1") (pin "14") (pinfunction "NC_14") (pintype "passive+no_connect"))
    )
    (net (code "96") (name "unconnected-(U1-NC-Pad15)") (class "Default")
      (node (ref "U1") (pin "15") (pinfunction "NC_15") (pintype "passive+no_connect"))
    )
    (net (code "97") (name "unconnected-(U1-NC-Pad16)") (class "Default")
      (node (ref "U1") (pin "16") (pinfunction "NC_16") (pintype "passive+no_connect"))
    )
    (net (code "98") (name "unconnected-(U1-NC-Pad17)") (class "Default")
      (node (ref "U1") (pin "17") (pinfunction "NC_17") (pintype "passive+no_connect"))
    )
    (net (code "99") (name "unconnected-(U2-PA4-Pad20)") (class "Default")
      (node (ref "U2") (pin "20") (pinfunction "PA4_20") (pintype "passive+no_connect"))
    )
    (net (code "100") (name "unconnected-(U2-PA14-Pad49)") (class "Default")
      (node (ref "U2") (pin "49") (pinfunction "PA14_49") (pintype "passive+no_connect"))
    )
    (net (code "101") (name "unconnected-(U2-PA15-Pad50)") (class "Default")
      (node (ref "U2") (pin "50") (pinfunction "PA15_50") (pintype "passive+no_connect"))
    )
    (net (code "102") (name "unconnected-(U2-PB3-Pad55)") (class "Default")
      (node (ref "U2") (pin "55") (pinfunction "PB3_55") (pintype "passive+no_connect"))
    )
    (net (code "103") (name "unconnected-(U2-PB4-Pad56)") (class "Default")
      (node (ref "U2") (pin "56") (pinfunction "PB4_56") (pintype "passive+no_connect"))
    )
    (net (code "104") (name "unconnected-(U2-PB8-Pad61)") (class "Default")
      (node (ref "U2") (pin "61") (pinfunction "PB8_61") (pintype "passive+no_connect"))
    )
    (net (code "105") (name "unconnected-(U2-PC14-OSC32_IN-Pad3)") (class "Default")
      (node (ref "U2") (pin "3") (pinfunction "PC14-OSC32_IN_3") (pintype "passive+no_connect"))
    )
    (net (code "106") (name "unconnected-(U2-PC15-OSC32_OUT-Pad4)") (class "Default")
      (node (ref "U2") (pin "4") (pinfunction "PC15-OSC32_OUT_4") (pintype "passive+no_connect"))
    )
    (net (code "107") (name "unconnected-(U4-CLKOUT-Pad7)") (class "Default")
      (node (ref "U4") (pin "7") (pinfunction "CLKOUT_7") (pintype "passive+no_connect"))
    )
    (net (code "108") (name "unconnected-(U4-HSYNC#-Pad18)") (class "Default")
      (node (ref "U4") (pin "18") (pinfunction "HSYNC#_18") (pintype "passive+no_connect"))
    )
    (net (code "109") (name "unconnected-(U4-LOS-Pad12)") (class "Default")
      (node (ref "U4") (pin "12") (pinfunction "LOS_12") (pintype "passive+no_connect"))
    )
    (net (code "110") (name "unconnected-(U4-NC-Pad1)") (class "Default")
      (node (ref "U4") (pin "1") (pinfunction "NC_1") (pintype "passive+no_connect"))
    )
    (net (code "111") (name "unconnected-(U4-NC-Pad2)") (class "Default")
      (node (ref "U4") (pin "2") (pinfunction "NC_2") (pintype "passive+no_connect"))
    )
    (net (code "112") (name "unconnected-(U4-NC-Pad14)") (class "Default")
      (node (ref "U4") (pin "14") (pinfunction "NC_14") (pintype "passive+no_connect"))
    )
    (net (code "113") (name "unconnected-(U4-NC-Pad15)") (class "Default")
      (node (ref "U4") (pin "15") (pinfunction "NC_15") (pintype "passive+no_connect"))
    )
    (net (code "114") (name "unconnected-(U4-NC-Pad16)") (class "Default")
      (node (ref "U4") (pin "16") (pinfunction "NC_16") (pintype "passive+no_connect"))
    )
    (net (code "115") (name "unconnected-(U4-NC-Pad27)") (class "Default")
      (node (ref "U4") (pin "27") (pinfunction "NC_27") (pintype "passive+no_connect"))
    )
    (net (code "116") (name "unconnected-(U4-NC-Pad28)") (class "Default")
      (node (ref "U4") (pin "28") (pinfunction "NC_28") (pintype "passive+no_connect"))
    )
    (net (code "117") (name "unconnected-(U4-SYNC_IN-Pad13)") (class "Default")
      (node (ref "U4") (pin "13") (pinfunction "SYNC_IN_13") (pintype "passive+no_connect"))
    )
    (net (code "118") (name "unconnected-(U4-VSYNC#-Pad17)") (class "Default")
      (node (ref "U4") (pin "17") (pinfunction "VSYNC#_17") (pintype "passive+no_connect"))
    )
    (net (code "119") (name "unconnected-(U6-AUX_CL-Pad7)") (class "Default")
      (node (ref "U6") (pin "7") (pinfunction "AUX_CL_7") (pintype "passive+no_connect"))
    )
    (net (code "120") (name "unconnected-(U6-AUX_DA-Pad21)") (class "Default")
      (node (ref "U6") (pin "21") (pinfunction "AUX_DA_21") (pintype "passive+no_connect"))
    )
    (net (code "121") (name "unconnected-(U6-NC-Pad1)") (class "Default")
      (node (ref "U6") (pin "1") (pinfunction "NC_1") (pintype "passive+no_connect"))
    )
    (net (code "122") (name "unconnected-(U6-NC-Pad2)") (class "Default")
      (node (ref "U6") (pin "2") (pinfunction "NC_2") (pintype "passive+no_connect"))
    )
    (net (code "123") (name "unconnected-(U6-NC-Pad3)") (class "Default")
      (node (ref "U6") (pin "3") (pinfunction "NC_3") (pintype "passive+no_connect"))
    )
    (net (code "124") (name "unconnected-(U6-NC-Pad4)") (class "Default")
      (node (ref "U6") (pin "4") (pinfunction "NC_4") (pintype "passive+no_connect"))
    )
    (net (code "125") (name "unconnected-(U6-NC-Pad5)") (class "Default")
      (node (ref "U6") (pin "5") (pinfunction "NC_5") (pintype "passive+no_connect"))
    )
    (net (code "126") (name "unconnected-(U6-NC-Pad6)") (class "Default")
      (node (ref "U6") (pin "6") (pinfunction "NC_6") (pintype "passive+no_connect"))
    )
    (net (code "127") (name "unconnected-(U6-NC-Pad14)") (class "Default")
      (node (ref "U6") (pin "14") (pinfunction "NC_14") (pintype "passive+no_connect"))
    )
    (net (code "128") (name "unconnected-(U6-NC-Pad15)") (class "Default")
      (node (ref "U6") (pin "15") (pinfunction "NC_15") (pintype "passive+no_connect"))
    )
    (net (code "129") (name "unconnected-(U6-NC-Pad16)") (class "Default")
      (node (ref "U6") (pin "16") (pinfunction "NC_16") (pintype "passive+no_connect"))
    )
    (net (code "130") (name "unconnected-(U6-NC-Pad17)") (class "Default")
      (node (ref "U6") (pin "17") (pinfunction "NC_17") (pintype "passive+no_connect"))
    )
    (net (code "131") (name "unconnected-(U6-RESV-Pad19)") (class "Default")
      (node (ref "U6") (pin "19") (pinfunction "RESV_19") (pintype "passive+no_connect"))
    )
    (net (code "132") (name "unconnected-(U8-HOLD#(IO3)-Pad7)") (class "Default")
      (node (ref "U8") (pin "7") (pinfunction "HOLD#(IO3)_7") (pintype "passive+no_connect"))
    )
    (net (code "133") (name "unconnected-(U8-WP#(IO2)-Pad3)") (class "Default")
      (node (ref "U8") (pin "3") (pinfunction "WP#(IO2)_3") (pintype "passive+no_connect"))
    )
  )
)
